# 2012_FDP_Generic_Port_Strat.net
KiCad netlist of a schematic drawn in Altium Designer
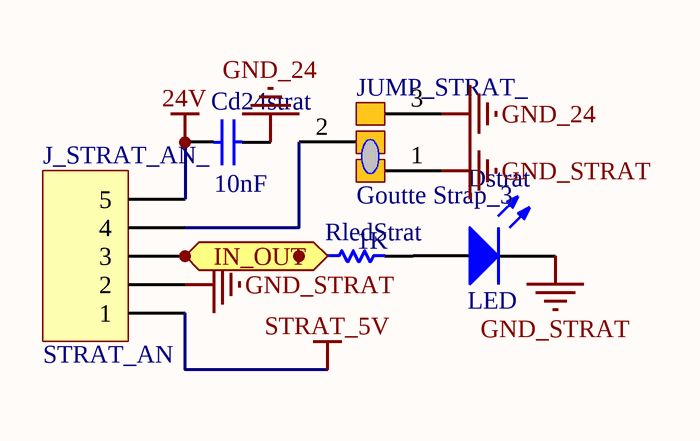
[diagram p0: 2012_FDP_Generic_Port_Strat.SchDoc]

(export (version "E")
  (design (tool "Eeschema 10.0.6"))
  (components
    (comp (ref "Cd24strat")
      (value "10nF")
      (footprint "C0805_N")
      (description "Capacitor")
      (fields (field (name "PUBLISHER") "Altium Limited"))
      (libsource (lib "_ROBOT") (part "Condensateur"))
    )
    (comp (ref "Dstrat")
      (value "LED")
      (footprint "LED_0805")
      (description "Typical LED")
      (fields (field (name "PUBLISHER") "Altium Limited"))
      (libsource (lib "_ROBOT") (part "LED"))
    )
    (comp (ref "JUMP_STRAT_")
      (value "Goutte Strap_3")
      (footprint "Goutte Strap_3")
      (fields (field (name "PUBLISHER") "Damien Guitton"))
      (libsource (lib "DG_Connecteur") (part "Goutte Strap_3"))
    )
    (comp (ref "J_STRAT_AN_")
      (value "STRAT_AN")
      (footprint "HE14_5")
      (description "Header, 5-Pin")
      (fields (field (name "PUBLISHER") "Altium Limited"))
      (libsource (lib "Connecteur") (part "BARRETTE5"))
    )
    (comp (ref "RledStrat")
      (value "1K")
      (footprint "R1206_N")
      (description "Resistor")
      (fields (field (name "PUBLISHER") "Altium Limited"))
      (libsource (lib "_ROBOT") (part "Resistor"))
    )
  )
  (nets
    (net (code "1") (name "/IN_OUT") (class "Default")
      (node (ref "J_STRAT_AN_") (pin "3") (pinfunction "3_3") (pintype "passive"))
      (node (ref "RledStrat") (pin "1") (pinfunction "1_1") (pintype "passive"))
    )
    (net (code "2") (name "24V") (class "Default")
      (node (ref "Cd24strat") (pin "1") (pinfunction "1_1") (pintype "passive"))
      (node (ref "J_STRAT_AN_") (pin "5") (pinfunction "5_5") (pintype "passive"))
    )
    (net (code "3") (name "GND_24") (class "Default")
      (node (ref "Cd24strat") (pin "2") (pinfunction "2_2") (pintype "passive"))
      (node (ref "JUMP_STRAT_") (pin "3") (pinfunction "3_3") (pintype "passive"))
    )
    (net (code "4") (name "GND_STRAT") (class "Default")
      (node (ref "Dstrat") (pin "2") (pinfunction "K_2") (pintype "passive"))
      (node (ref "JUMP_STRAT_") (pin "1") (pinfunction "1_1") (pintype "passive"))
      (node (ref "J_STRAT_AN_") (pin "2") (pinfunction "2_2") (pintype "passive"))
    )
    (net (code "5") (name "Net-(Dstrat-A)") (class "Default")
      (node (ref "Dstrat") (pin "1") (pinfunction "A_1") (pintype "passive"))
      (node (ref "RledStrat") (pin "2") (pinfunction "2_2") (pintype "passive"))
    )
    (net (code "6") (name "Net-(JUMP_STRAT_-Pad2)") (class "Default")
      (node (ref "JUMP_STRAT_") (pin "2") (pinfunction "2_2") (pintype "passive"))
      (node (ref "J_STRAT_AN_") (pin "4") (pinfunction "4_4") (pintype "passive"))
    )
    (net (code "7") (name "STRAT_5V") (class "Default")
      (node (ref "J_STRAT_AN_") (pin "1") (pinfunction "1_1") (pintype "passive"))
    )
  )
)
